# aKaReZa75_eBoard_STM32F103C8__STM32F103C.net
KiCad netlist of a schematic drawn in Altium Designer
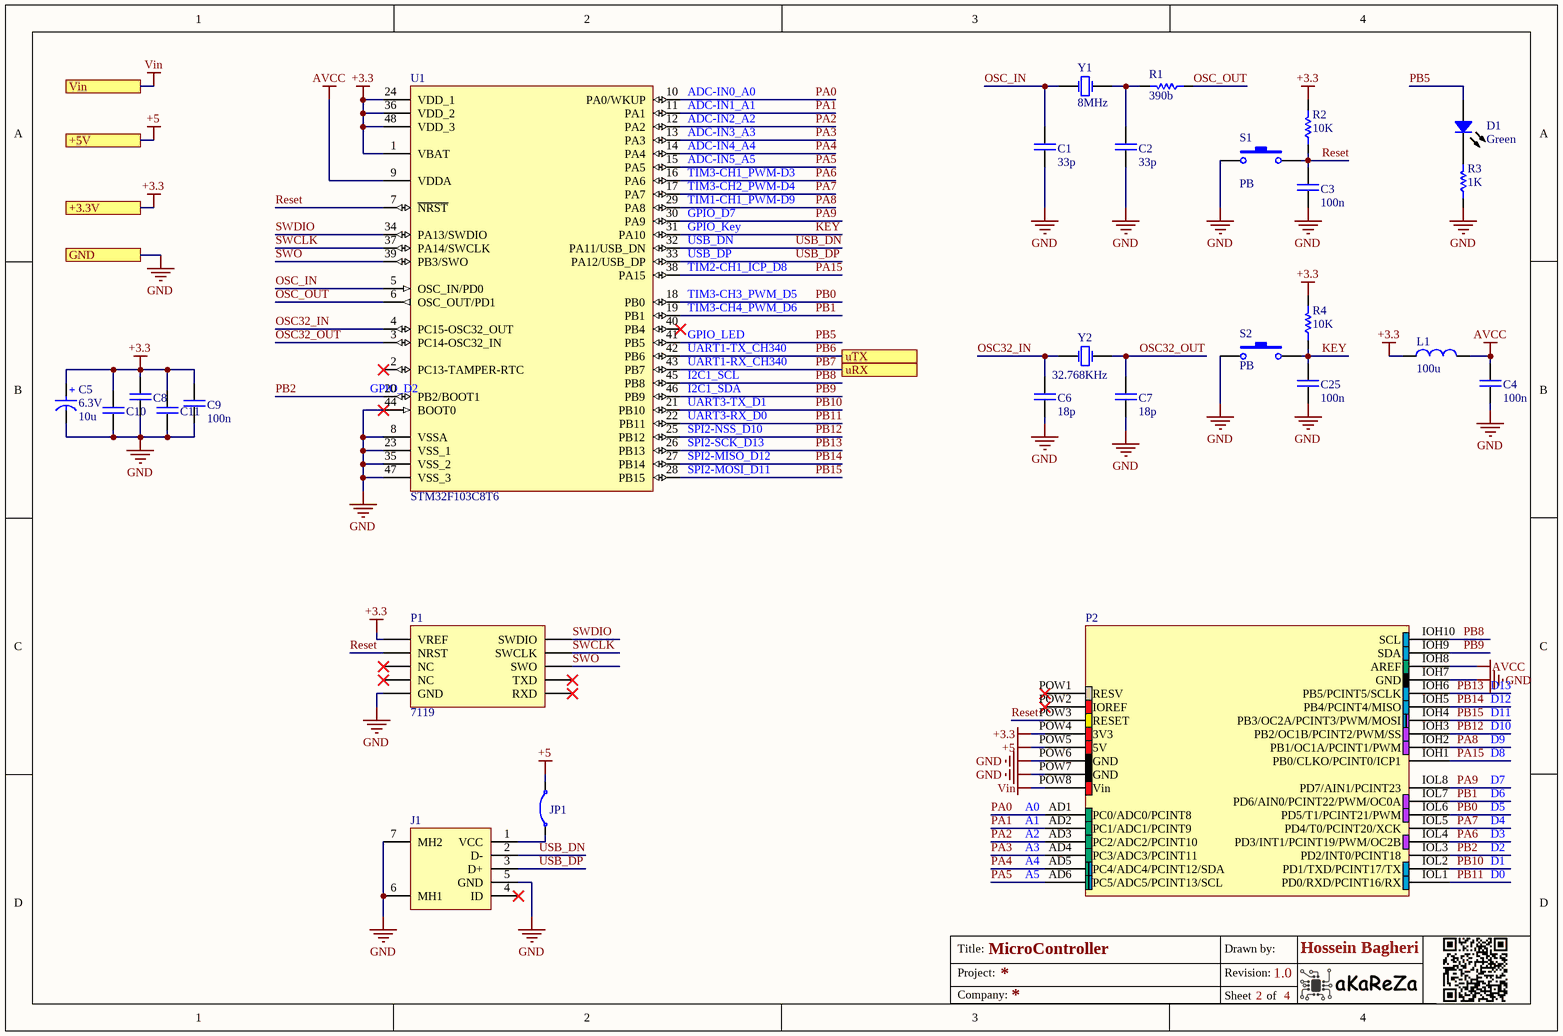
[diagram p0: aKaReZa75_eBoard_STM32F103C8__STM32F103C8__MicroController.SchDoc]

(export (version "E")
  (design (tool "Eeschema 10.0.6"))
  (components
    (comp (ref "C1")
      (value "33p")
      (footprint "CAP 0603/1608")
      (description "Bipolar ceramic capacitor SMD")
      (fields (field (name "VALIDATION") "Valid"))
      (libsource (lib "aKaReZa") (part "Cap_Multi_SMD"))
    )
    (comp (ref "C2")
      (value "33p")
      (footprint "CAP 0603/1608")
      (description "Bipolar ceramic capacitor SMD")
      (fields (field (name "VALIDATION") "Valid"))
      (libsource (lib "aKaReZa") (part "Cap_Multi_SMD"))
    )
    (comp (ref "C3")
      (value "100n")
      (footprint "CAP 0805/2012")
      (description "Bipolar ceramic capacitor SMD")
      (fields (field (name "VALIDATION") "Valid"))
      (libsource (lib "aKaReZa") (part "Cap_Multi_SMD_100nF_0805"))
    )
    (comp (ref "C4")
      (value "100n")
      (footprint "CAP 0805/2012")
      (description "Bipolar ceramic capacitor SMD")
      (fields (field (name "VALIDATION") "Valid"))
      (libsource (lib "aKaReZa") (part "Cap_Multi_SMD_100nF_0805"))
    )
    (comp (ref "C5")
      (value "10u")
      (footprint "SMT_C_Tantalum_A")
      (description "Tantalum Capacitor,TAJ Series-SMD")
      (fields (field (name "RATING") "6.3V") (field (name "VALIDATION") "Valid"))
      (libsource (lib "aKaReZa") (part "Cap_Tantalum"))
    )
    (comp (ref "C6")
      (value "18p")
      (footprint "CAP 0603/1608")
      (description "Bipolar ceramic capacitor SMD")
      (fields (field (name "VALIDATION") "Valid"))
      (libsource (lib "aKaReZa") (part "Cap_Multi_SMD"))
    )
    (comp (ref "C7")
      (value "18p")
      (footprint "CAP 0603/1608")
      (description "Bipolar ceramic capacitor SMD")
      (fields (field (name "VALIDATION") "Valid"))
      (libsource (lib "aKaReZa") (part "Cap_Multi_SMD"))
    )
    (comp (ref "C8")
      (value "100n")
      (footprint "CAP 0805/2012")
      (description "Bipolar ceramic capacitor SMD")
      (fields (field (name "VALIDATION") "Valid"))
      (libsource (lib "aKaReZa") (part "Cap_Multi_SMD_100nF_0805"))
    )
    (comp (ref "C9")
      (value "100n")
      (footprint "CAP 0805/2012")
      (description "Bipolar ceramic capacitor SMD")
      (fields (field (name "VALIDATION") "Valid"))
      (libsource (lib "aKaReZa") (part "Cap_Multi_SMD_100nF_0805"))
    )
    (comp (ref "C10")
      (value "100n")
      (footprint "CAP 0805/2012")
      (description "Bipolar ceramic capacitor SMD")
      (fields (field (name "VALIDATION") "Valid"))
      (libsource (lib "aKaReZa") (part "Cap_Multi_SMD_100nF_0805"))
    )
    (comp (ref "C11")
      (value "100n")
      (footprint "CAP 0805/2012")
      (description "Bipolar ceramic capacitor SMD")
      (fields (field (name "VALIDATION") "Valid"))
      (libsource (lib "aKaReZa") (part "Cap_Multi_SMD_100nF_0805"))
    )
    (comp (ref "C25")
      (value "100n")
      (footprint "CAP 0805/2012")
      (description "Bipolar ceramic capacitor SMD")
      (fields (field (name "VALIDATION") "Valid"))
      (libsource (lib "aKaReZa") (part "Cap_Multi_SMD_100nF_0805"))
    )
    (comp (ref "D1")
      (value "Green")
      (footprint "LED 0805/2012 GREEN")
      (description "LED")
      (fields (field (name "VALIDATION") "Valid"))
      (libsource (lib "aKaReZa") (part "Semi_LED_SMD"))
    )
    (comp (ref "J1")
      (value "Micro")
      (footprint "USB_Micro_Standard")
      (description "USB micro female")
      (fields (field (name "VALIDATION") "NT"))
      (libsource (lib "aKaReZa") (part "Con_USB2_Micro"))
    )
    (comp (ref "JP1")
      (value "Jumper")
      (footprint "RESC2012M (0805)")
      (description "Jumper Component")
      (fields (field (name "VALIDATION") "Valid"))
      (libsource (lib "aKaReZa") (part "Other_Elec_Jumper_0805"))
    )
    (comp (ref "L1")
      (value "100u")
      (footprint "IND0805")
      (description "Inductor")
      (fields (field (name "VALIDATION") "Valid"))
      (libsource (lib "aKaReZa") (part "Ind_SMD_0805"))
    )
    (comp (ref "P1")
      (value "STLinkV3-minie")
      (footprint "IDC2.54-10PIN")
      (description "STLINK-V3MINIE debugger/programmer IDC probe for STM32 microcontrollers")
      (fields (field (name "INFLOW") "7119") (field (name "VALIDATION") "NT"))
      (libsource (lib "aKaReZa") (part "Con_Prog_STLinkV3_SWD"))
    )
    (comp (ref "P2")
      (value "UNO")
      (footprint "ARDUINO_UNO_CONNECTOR")
      (description "Arduino UNO Connector")
      (fields (field (name "VALIDATION") "NT"))
      (libsource (lib "aKaReZa") (part "Con_Arduino_UNO_Con"))
    )
    (comp (ref "R1")
      (value "390b")
      (footprint "RES 0805 (2012X06L)")
      (description "Resistor")
      (fields (field (name "VALIDATION") "Valid"))
      (libsource (lib "aKaReZa") (part "Res_SMD_0805"))
    )
    (comp (ref "R2")
      (value "10K")
      (footprint "RES 0805 (2012X06L)")
      (description "Resistor")
      (fields (field (name "VALIDATION") "Valid"))
      (libsource (lib "aKaReZa") (part "Res_SMD_0805"))
    )
    (comp (ref "R3")
      (value "1K")
      (footprint "RES 0805 (2012X06L)")
      (description "Resistor")
      (fields (field (name "VALIDATION") "Valid"))
      (libsource (lib "aKaReZa") (part "Res_SMD_0805"))
    )
    (comp (ref "R4")
      (value "10K")
      (footprint "RES 0805 (2012X06L)")
      (description "Resistor")
      (fields (field (name "VALIDATION") "Valid"))
      (libsource (lib "aKaReZa") (part "Res_SMD_0805"))
    )
    (comp (ref "S1")
      (value "PB")
      (footprint "SW_PB_SMD_2PIN_SPST_6X3X2")
      (description "SMT Tactile ‎Switch")
      (fields (field (name "VALIDATION") "Valid"))
      (libsource (lib "aKaReZa") (part "SW_PushButton_2_SMD"))
    )
    (comp (ref "S2")
      (value "PB")
      (footprint "SW_PB_SMD_2PIN_SPST_6X3X2")
      (description "SMT Tactile ‎Switch")
      (fields (field (name "VALIDATION") "Valid"))
      (libsource (lib "aKaReZa") (part "SW_PushButton_2_SMD"))
    )
    (comp (ref "U1")
      (value "STM32F103C8T6")
      (footprint "LQFP48_N")
      (description "32-Bit mircrocontroller")
      (fields (field (name "VALIDATION") "NT"))
      (libsource (lib "aKaReZa") (part "IC_MCU_STM32F103C8T6"))
    )
    (comp (ref "Y1")
      (value "8MHz")
      (footprint "XTL_2_5032")
      (description "Crystal Oscillator")
      (fields (field (name "VALIDATION") "NT"))
      (libsource (lib "aKaReZa") (part "Other_Elec_Xtal_8MHZ_SMD"))
    )
    (comp (ref "Y2")
      (value "32.768KHz")
      (footprint "XTL_2_3215")
      (description "Crystal Oscillator")
      (fields (field (name "VALIDATION") "NT"))
      (libsource (lib "aKaReZa") (part "Other_Elec_Xtal_32.768K_SMD"))
    )
  )
  (nets
    (net (code "1") (name "+3.3") (class "Default")
      (node (ref "C10") (pin "1") (pinfunction "1_1") (pintype "passive"))
      (node (ref "C11") (pin "1") (pinfunction "1_1") (pintype "passive"))
      (node (ref "C5") (pin "1") (pinfunction "+_1") (pintype "passive"))
      (node (ref "C8") (pin "1") (pinfunction "1_1") (pintype "passive"))
      (node (ref "C9") (pin "1") (pinfunction "1_1") (pintype "passive"))
      (node (ref "L1") (pin "1") (pinfunction "1_1") (pintype "passive"))
      (node (ref "P1") (pin "10") (pinfunction "VREF_10") (pintype "passive"))
      (node (ref "P2") (pin "POW4") (pinfunction "3V3_POW4") (pintype "passive"))
      (node (ref "R2") (pin "2") (pinfunction "2_2") (pintype "passive"))
      (node (ref "R4") (pin "2") (pinfunction "2_2") (pintype "passive"))
      (node (ref "U1") (pin "1") (pinfunction "VBAT_1") (pintype "power_in"))
      (node (ref "U1") (pin "24") (pinfunction "VDD_1_24") (pintype "power_in"))
      (node (ref "U1") (pin "36") (pinfunction "VDD_2_36") (pintype "power_in"))
      (node (ref "U1") (pin "48") (pinfunction "VDD_3_48") (pintype "power_in"))
    )
    (net (code "2") (name "+5") (class "Default")
      (node (ref "JP1") (pin "2") (pinfunction "2_2") (pintype "passive"))
      (node (ref "P2") (pin "POW5") (pinfunction "5V_POW5") (pintype "passive"))
    )
    (net (code "3") (name "/KEY") (class "Default")
      (node (ref "C25") (pin "1") (pinfunction "1_1") (pintype "passive"))
      (node (ref "R4") (pin "1") (pinfunction "1_1") (pintype "passive"))
      (node (ref "S2") (pin "1") (pinfunction "1_1") (pintype "passive"))
      (node (ref "U1") (pin "31") (pinfunction "PA10_31") (pintype "bidirectional"))
    )
    (net (code "4") (name "/OSC32_IN") (class "Default")
      (node (ref "C6") (pin "1") (pinfunction "1_1") (pintype "passive"))
      (node (ref "U1") (pin "4") (pinfunction "PC15-OSC32_OUT_4") (pintype "bidirectional"))
      (node (ref "Y2") (pin "1") (pinfunction "OSC1_1") (pintype "passive"))
    )
    (net (code "5") (name "/OSC32_OUT") (class "Default")
      (node (ref "C7") (pin "1") (pinfunction "1_1") (pintype "passive"))
      (node (ref "U1") (pin "3") (pinfunction "PC14-OSC32_IN_3") (pintype "bidirectional"))
      (node (ref "Y2") (pin "2") (pinfunction "OSC2_2") (pintype "passive"))
    )
    (net (code "6") (name "/OSC_IN") (class "Default")
      (node (ref "C1") (pin "1") (pinfunction "1_1") (pintype "passive"))
      (node (ref "U1") (pin "5") (pinfunction "OSC_IN/PD0_5") (pintype "input"))
      (node (ref "Y1") (pin "1") (pinfunction "OSC1_1") (pintype "passive"))
    )
    (net (code "7") (name "/OSC_OUT") (class "Default")
      (node (ref "R1") (pin "1") (pinfunction "1_1") (pintype "passive"))
      (node (ref "U1") (pin "6") (pinfunction "OSC_OUT/PD1_6") (pintype "output"))
    )
    (net (code "8") (name "/PA0") (class "Default")
      (node (ref "P2") (pin "AD1") (pinfunction "PC0/ADC0/PCINT8_AD1") (pintype "passive"))
      (node (ref "U1") (pin "10") (pinfunction "PA0/WKUP_10") (pintype "bidirectional"))
    )
    (net (code "9") (name "/PA1") (class "Default")
      (node (ref "P2") (pin "AD2") (pinfunction "PC1/ADC1/PCINT9_AD2") (pintype "passive"))
      (node (ref "U1") (pin "11") (pinfunction "PA1_11") (pintype "bidirectional"))
    )
    (net (code "10") (name "/PA2") (class "Default")
      (node (ref "P2") (pin "AD3") (pinfunction "PC2/ADC2/PCINT10_AD3") (pintype "passive"))
      (node (ref "U1") (pin "12") (pinfunction "PA2_12") (pintype "bidirectional"))
    )
    (net (code "11") (name "/PA3") (class "Default")
      (node (ref "P2") (pin "AD4") (pinfunction "PC3/ADC3/PCINT11_AD4") (pintype "passive"))
      (node (ref "U1") (pin "13") (pinfunction "PA3_13") (pintype "bidirectional"))
    )
    (net (code "12") (name "/PA4") (class "Default")
      (node (ref "P2") (pin "AD5") (pinfunction "PC4/ADC4/PCINT12/SDA_AD5") (pintype "passive"))
      (node (ref "U1") (pin "14") (pinfunction "PA4_14") (pintype "bidirectional"))
    )
    (net (code "13") (name "/PA5") (class "Default")
      (node (ref "P2") (pin "AD6") (pinfunction "PC5/ADC5/PCINT13/SCL_AD6") (pintype "passive"))
      (node (ref "U1") (pin "15") (pinfunction "PA5_15") (pintype "bidirectional"))
    )
    (net (code "14") (name "/PA6") (class "Default")
      (node (ref "P2") (pin "IOL4") (pinfunction "PD3/INT1/PCINT19/PWM/OC2B_IOL4") (pintype "passive"))
      (node (ref "U1") (pin "16") (pinfunction "PA6_16") (pintype "bidirectional"))
    )
    (net (code "15") (name "/PA7") (class "Default")
      (node (ref "P2") (pin "IOL5") (pinfunction "PD4/T0/PCINT20/XCK_IOL5") (pintype "passive"))
      (node (ref "U1") (pin "17") (pinfunction "PA7_17") (pintype "bidirectional"))
    )
    (net (code "16") (name "/PA8") (class "Default")
      (node (ref "P2") (pin "IOH2") (pinfunction "PB1/OC1A/PCINT1/PWM_IOH2") (pintype "passive"))
      (node (ref "U1") (pin "29") (pinfunction "PA8_29") (pintype "bidirectional"))
    )
    (net (code "17") (name "/PA9") (class "Default")
      (node (ref "P2") (pin "IOL8") (pinfunction "PD7/AIN1/PCINT23_IOL8") (pintype "passive"))
      (node (ref "U1") (pin "30") (pinfunction "PA9_30") (pintype "bidirectional"))
    )
    (net (code "18") (name "/PA15") (class "Default")
      (node (ref "P2") (pin "IOH1") (pinfunction "PB0/CLKO/PCINT0/ICP1_IOH1") (pintype "passive"))
      (node (ref "U1") (pin "38") (pinfunction "PA15_38") (pintype "bidirectional"))
    )
    (net (code "19") (name "/PB0") (class "Default")
      (node (ref "P2") (pin "IOL6") (pinfunction "PD5/T1/PCINT21/PWM_IOL6") (pintype "passive"))
      (node (ref "U1") (pin "18") (pinfunction "PB0_18") (pintype "bidirectional"))
    )
    (net (code "20") (name "/PB1") (class "Default")
      (node (ref "P2") (pin "IOL7") (pinfunction "PD6/AIN0/PCINT22/PWM/OC0A_IOL7") (pintype "passive"))
      (node (ref "U1") (pin "19") (pinfunction "PB1_19") (pintype "bidirectional"))
    )
    (net (code "21") (name "/PB2") (class "Default")
      (node (ref "P2") (pin "IOL3") (pinfunction "PD2/INT0/PCINT18_IOL3") (pintype "passive"))
      (node (ref "U1") (pin "20") (pinfunction "PB2/BOOT1_20") (pintype "bidirectional"))
    )
    (net (code "22") (name "/PB5") (class "Default")
      (node (ref "D1") (pin "1") (pinfunction "1_1") (pintype "passive"))
      (node (ref "U1") (pin "41") (pinfunction "PB5_41") (pintype "bidirectional"))
    )
    (net (code "23") (name "/PB6") (class "Default")
      (node (ref "U1") (pin "42") (pinfunction "PB6_42") (pintype "bidirectional"))
    )
    (net (code "24") (name "/PB7") (class "Default")
      (node (ref "U1") (pin "43") (pinfunction "PB7_43") (pintype "bidirectional"))
    )
    (net (code "25") (name "/PB8") (class "Default")
      (node (ref "P2") (pin "IOH10") (pinfunction "SCL_IOH10") (pintype "passive"))
      (node (ref "U1") (pin "45") (pinfunction "PB8_45") (pintype "bidirectional"))
    )
    (net (code "26") (name "/PB9") (class "Default")
      (node (ref "P2") (pin "IOH9") (pinfunction "SDA_IOH9") (pintype "passive"))
      (node (ref "U1") (pin "46") (pinfunction "PB9_46") (pintype "bidirectional"))
    )
    (net (code "27") (name "/PB10") (class "Default")
      (node (ref "P2") (pin "IOL2") (pinfunction "PD1/TXD/PCINT17/TX_IOL2") (pintype "passive"))
      (node (ref "U1") (pin "21") (pinfunction "PB10_21") (pintype "bidirectional"))
    )
    (net (code "28") (name "/PB11") (class "Default")
      (node (ref "P2") (pin "IOL1") (pinfunction "PD0/RXD/PCINT16/RX_IOL1") (pintype "passive"))
      (node (ref "U1") (pin "22") (pinfunction "PB11_22") (pintype "bidirectional"))
    )
    (net (code "29") (name "/PB12") (class "Default")
      (node (ref "P2") (pin "IOH3") (pinfunction "PB2/OC1B/PCINT2/PWM/SS_IOH3") (pintype "passive"))
      (node (ref "U1") (pin "25") (pinfunction "PB12_25") (pintype "bidirectional"))
    )
    (net (code "30") (name "/PB13") (class "Default")
      (node (ref "P2") (pin "IOH6") (pinfunction "PB5/PCINT5/SCLK_IOH6") (pintype "passive"))
      (node (ref "U1") (pin "26") (pinfunction "PB13_26") (pintype "bidirectional"))
    )
    (net (code "31") (name "/PB14") (class "Default")
      (node (ref "P2") (pin "IOH5") (pinfunction "PB4/PCINT4/MISO_IOH5") (pintype "passive"))
      (node (ref "U1") (pin "27") (pinfunction "PB14_27") (pintype "bidirectional"))
    )
    (net (code "32") (name "/PB15") (class "Default")
      (node (ref "P2") (pin "IOH4") (pinfunction "PB3/OC2A/PCINT3/PWM/MOSI_IOH4") (pintype "passive"))
      (node (ref "U1") (pin "28") (pinfunction "PB15_28") (pintype "bidirectional"))
    )
    (net (code "33") (name "/Reset") (class "Default")
      (node (ref "C3") (pin "1") (pinfunction "1_1") (pintype "passive"))
      (node (ref "P1") (pin "8") (pinfunction "NRST_8") (pintype "passive"))
      (node (ref "P2") (pin "POW3") (pinfunction "RESET_POW3") (pintype "passive"))
      (node (ref "R2") (pin "1") (pinfunction "1_1") (pintype "passive"))
      (node (ref "S1") (pin "2") (pinfunction "2_2") (pintype "passive"))
      (node (ref "U1") (pin "7") (pinfunction "~{NRST}_7") (pintype "bidirectional"))
    )
    (net (code "34") (name "/SWCLK") (class "Default")
      (node (ref "P1") (pin "7") (pinfunction "SWCLK_7") (pintype "passive"))
      (node (ref "U1") (pin "37") (pinfunction "PA14/SWCLK_37") (pintype "bidirectional"))
    )
    (net (code "35") (name "/SWDIO") (class "Default")
      (node (ref "P1") (pin "5") (pinfunction "SWDIO_5") (pintype "passive"))
      (node (ref "U1") (pin "34") (pinfunction "PA13/SWDIO_34") (pintype "bidirectional"))
    )
    (net (code "36") (name "/SWO") (class "Default")
      (node (ref "P1") (pin "9") (pinfunction "SWO_9") (pintype "passive"))
      (node (ref "U1") (pin "39") (pinfunction "PB3/SWO_39") (pintype "bidirectional"))
    )
    (net (code "37") (name "/USB_DN") (class "Default")
      (node (ref "J1") (pin "2") (pinfunction "D-_2") (pintype "passive"))
      (node (ref "U1") (pin "32") (pinfunction "PA11/USB_DN_32") (pintype "bidirectional"))
    )
    (net (code "38") (name "/USB_DP") (class "Default")
      (node (ref "J1") (pin "3") (pinfunction "D+_3") (pintype "passive"))
      (node (ref "U1") (pin "33") (pinfunction "PA12/USB_DP_33") (pintype "bidirectional"))
    )
    (net (code "39") (name "AVCC") (class "Default")
      (node (ref "C4") (pin "1") (pinfunction "1_1") (pintype "passive"))
      (node (ref "L1") (pin "2") (pinfunction "2_2") (pintype "passive"))
      (node (ref "P2") (pin "IOH8") (pinfunction "AREF_IOH8") (pintype "passive"))
      (node (ref "U1") (pin "9") (pinfunction "VDDA_9") (pintype "power_in"))
    )
    (net (code "40") (name "GND") (class "Default")
      (node (ref "C1") (pin "2") (pinfunction "2_2") (pintype "passive"))
      (node (ref "C10") (pin "2") (pinfunction "2_2") (pintype "passive"))
      (node (ref "C11") (pin "2") (pinfunction "2_2") (pintype "passive"))
      (node (ref "C2") (pin "2") (pinfunction "2_2") (pintype "passive"))
      (node (ref "C25") (pin "2") (pinfunction "2_2") (pintype "passive"))
      (node (ref "C3") (pin "2") (pinfunction "2_2") (pintype "passive"))
      (node (ref "C4") (pin "2") (pinfunction "2_2") (pintype "passive"))
      (node (ref "C5") (pin "2") (pinfunction "-_2") (pintype "passive"))
      (node (ref "C6") (pin "2") (pinfunction "2_2") (pintype "passive"))
      (node (ref "C7") (pin "2") (pinfunction "2_2") (pintype "passive"))
      (node (ref "C8") (pin "2") (pinfunction "2_2") (pintype "passive"))
      (node (ref "C9") (pin "2") (pinfunction "2_2") (pintype "passive"))
      (node (ref "J1") (pin "5") (pinfunction "GND_5") (pintype "passive"))
      (node (ref "J1") (pin "6") (pinfunction "MH1_6") (pintype "passive"))
      (node (ref "J1") (pin "7") (pinfunction "MH2_7") (pintype "passive"))
      (node (ref "P1") (pin "2") (pinfunction "GND_2") (pintype "passive"))
      (node (ref "P2") (pin "IOH7") (pinfunction "GND_IOH7") (pintype "passive"))
      (node (ref "P2") (pin "POW6") (pinfunction "GND_POW6") (pintype "passive"))
      (node (ref "P2") (pin "POW7") (pinfunction "GND_POW7") (pintype "passive"))
      (node (ref "R3") (pin "1") (pinfunction "1_1") (pintype "passive"))
      (node (ref "S1") (pin "1") (pinfunction "1_1") (pintype "passive"))
      (node (ref "S2") (pin "2") (pinfunction "2_2") (pintype "passive"))
      (node (ref "U1") (pin "23") (pinfunction "VSS_1_23") (pintype "power_in"))
      (node (ref "U1") (pin "35") (pinfunction "VSS_2_35") (pintype "power_in"))
      (node (ref "U1") (pin "44") (pinfunction "BOOT0_44") (pintype "input"))
      (node (ref "U1") (pin "47") (pinfunction "VSS_3_47") (pintype "power_in"))
      (node (ref "U1") (pin "8") (pinfunction "VSSA_8") (pintype "power_in"))
    )
    (net (code "41") (name "Net-(D1-Pad2)") (class "Default")
      (node (ref "D1") (pin "2") (pinfunction "2_2") (pintype "passive"))
      (node (ref "R3") (pin "2") (pinfunction "2_2") (pintype "passive"))
    )
    (net (code "42") (name "Net-(J1-VCC)") (class "Default")
      (node (ref "J1") (pin "1") (pinfunction "VCC_1") (pintype "passive"))
      (node (ref "JP1") (pin "1") (pinfunction "1_1") (pintype "passive"))
    )
    (net (code "43") (name "Net-(Y1-OSC2)") (class "Default")
      (node (ref "C2") (pin "1") (pinfunction "1_1") (pintype "passive"))
      (node (ref "R1") (pin "2") (pinfunction "2_2") (pintype "passive"))
      (node (ref "Y1") (pin "2") (pinfunction "OSC2_2") (pintype "passive"))
    )
    (net (code "44") (name "Vin") (class "Default")
      (node (ref "P2") (pin "POW8") (pinfunction "Vin_POW8") (pintype "passive"))
    )
    (net (code "45") (name "unconnected-(J1-ID-Pad4)") (class "Default")
      (node (ref "J1") (pin "4") (pinfunction "ID_4") (pintype "passive+no_connect"))
    )
    (net (code "46") (name "unconnected-(P1-NC-Pad1)") (class "Default")
      (node (ref "P1") (pin "1") (pinfunction "NC_1") (pintype "passive+no_connect"))
    )
    (net (code "47") (name "unconnected-(P1-NC-Pad3)") (class "Default")
      (node (ref "P1") (pin "3") (pinfunction "NC_3") (pintype "passive+no_connect"))
    )
    (net (code "48") (name "unconnected-(P1-RXD-Pad6)") (class "Default")
      (node (ref "P1") (pin "6") (pinfunction "RXD_6") (pintype "passive+no_connect"))
    )
    (net (code "49") (name "unconnected-(P1-TXD-Pad4)") (class "Default")
      (node (ref "P1") (pin "4") (pinfunction "TXD_4") (pintype "passive+no_connect"))
    )
    (net (code "50") (name "unconnected-(P2-IOREF-PadPOW2)") (class "Default")
      (node (ref "P2") (pin "POW2") (pinfunction "IOREF_POW2") (pintype "passive+no_connect"))
    )
    (net (code "51") (name "unconnected-(P2-RESV-PadPOW1)") (class "Default")
      (node (ref "P2") (pin "POW1") (pinfunction "RESV_POW1") (pintype "passive+no_connect"))
    )
    (net (code "52") (name "unconnected-(U1-PB4-Pad40)") (class "Default")
      (node (ref "U1") (pin "40") (pinfunction "PB4_40") (pintype "bidirectional+no_connect"))
    )
    (net (code "53") (name "unconnected-(U1-PC13-TAMPER-RTC-Pad2)") (class "Default")
      (node (ref "U1") (pin "2") (pinfunction "PC13-TAMPER-RTC_2") (pintype "bidirectional+no_connect"))
    )
  )
)
